# RPi_shield.net
KiCad netlist of a schematic drawn in EAGLE
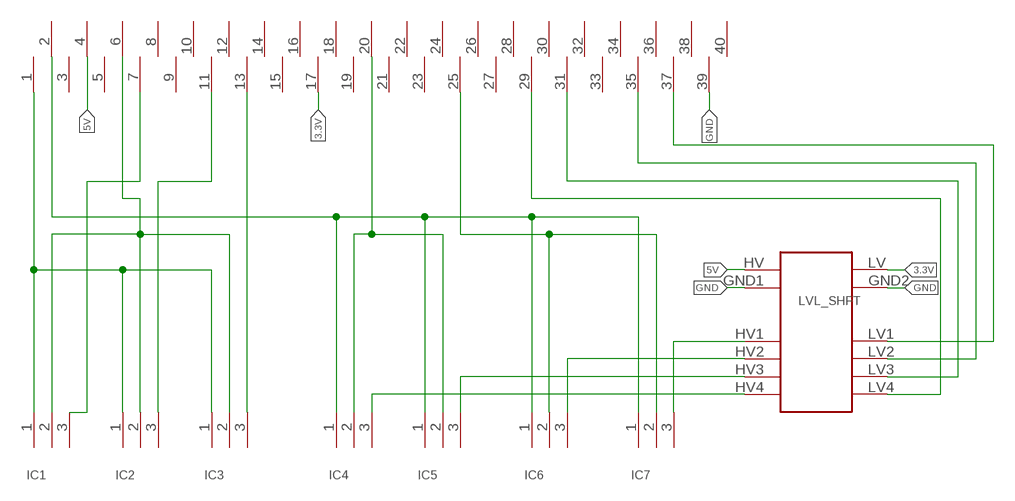
[diagram p0: schematic, sheet 1]

(export (version "E")
  (design (tool "Eeschema 10.0.6"))
  (components
    (comp (ref "IC1")
      (value "3,5MM_3PIN")
      (footprint "eagle-import:3,5MM_3PIN")
      (libsource (lib "eagle-import") (part "3,5MM_3PIN"))
    )
    (comp (ref "IC2")
      (value "3,5MM_3PIN")
      (footprint "eagle-import:3,5MM_3PIN")
      (libsource (lib "eagle-import") (part "3,5MM_3PIN"))
    )
    (comp (ref "IC3")
      (value "3,5MM_3PIN")
      (footprint "eagle-import:3,5MM_3PIN")
      (libsource (lib "eagle-import") (part "3,5MM_3PIN"))
    )
    (comp (ref "IC4")
      (value "3,5MM_3PIN")
      (footprint "eagle-import:3,5MM_3PIN")
      (libsource (lib "eagle-import") (part "3,5MM_3PIN"))
    )
    (comp (ref "IC5")
      (value "3,5MM_3PIN")
      (footprint "eagle-import:3,5MM_3PIN")
      (libsource (lib "eagle-import") (part "3,5MM_3PIN"))
    )
    (comp (ref "IC6")
      (value "3,5MM_3PIN")
      (footprint "eagle-import:3,5MM_3PIN")
      (libsource (lib "eagle-import") (part "3,5MM_3PIN"))
    )
    (comp (ref "IC7")
      (value "3,5MM_3PIN")
      (footprint "eagle-import:3,5MM_3PIN")
      (libsource (lib "eagle-import") (part "3,5MM_3PIN"))
    )
    (comp (ref "IC17")
      (value "40_PIN_2.54MM")
      (footprint "eagle-import:40_PIN_2.54MM")
      (libsource (lib "eagle-import") (part "40_PIN_2.54MM"))
    )
    (comp (ref "LVL_SHFT")
      (value "LVL_SHIFTER_4CH")
      (footprint "eagle-import:LVL_SHIFTER_4CH")
      (libsource (lib "eagle-import") (part "LVL_SHIFTER_4CH"))
    )
  )
  (nets
    (net (code "1") (name "3.3V") (class "Default")
      (node (ref "IC17") (pin "17") (pinfunction "P$17_17") (pintype "bidirectional"))
      (node (ref "LVL_SHFT") (pin "LV") (pinfunction "LV_LV") (pintype "bidirectional"))
    )
    (net (code "2") (name "5V") (class "Default")
      (node (ref "IC17") (pin "4") (pinfunction "P$4_4") (pintype "bidirectional"))
      (node (ref "LVL_SHFT") (pin "HV") (pinfunction "HV_HV") (pintype "bidirectional"))
    )
    (net (code "3") (name "GND") (class "Default")
      (node (ref "IC17") (pin "39") (pinfunction "P$39_39") (pintype "bidirectional"))
      (node (ref "LVL_SHFT") (pin "GND1") (pinfunction "GND1_GND1") (pintype "bidirectional"))
      (node (ref "LVL_SHFT") (pin "GND2") (pinfunction "GND2_GND2") (pintype "bidirectional"))
    )
    (net (code "4") (name "Net-(IC1-P$1)") (class "Default")
      (node (ref "IC1") (pin "1") (pinfunction "P$1_1") (pintype "bidirectional"))
      (node (ref "IC17") (pin "1") (pinfunction "P$1_1") (pintype "bidirectional"))
      (node (ref "IC2") (pin "1") (pinfunction "P$1_1") (pintype "bidirectional"))
      (node (ref "IC3") (pin "1") (pinfunction "P$1_1") (pintype "bidirectional"))
    )
    (net (code "5") (name "Net-(IC1-P$2)") (class "Default")
      (node (ref "IC1") (pin "2") (pinfunction "P$2_2") (pintype "bidirectional"))
      (node (ref "IC17") (pin "6") (pinfunction "P$6_6") (pintype "bidirectional"))
      (node (ref "IC2") (pin "2") (pinfunction "P$2_2") (pintype "bidirectional"))
      (node (ref "IC3") (pin "2") (pinfunction "P$2_2") (pintype "bidirectional"))
    )
    (net (code "6") (name "Net-(IC1-P$3)") (class "Default")
      (node (ref "IC1") (pin "3") (pinfunction "P$3_3") (pintype "bidirectional"))
      (node (ref "IC17") (pin "7") (pinfunction "P$7_7") (pintype "bidirectional"))
    )
    (net (code "7") (name "Net-(IC4-P$3)") (class "Default")
      (node (ref "IC4") (pin "3") (pinfunction "P$3_3") (pintype "bidirectional"))
      (node (ref "LVL_SHFT") (pin "HV4") (pinfunction "HV4_HV4") (pintype "bidirectional"))
    )
    (net (code "8") (name "Net-(IC5-P$3)") (class "Default")
      (node (ref "IC5") (pin "3") (pinfunction "P$3_3") (pintype "bidirectional"))
      (node (ref "LVL_SHFT") (pin "HV3") (pinfunction "HV3_HV3") (pintype "bidirectional"))
    )
    (net (code "9") (name "Net-(IC6-P$3)") (class "Default")
      (node (ref "IC6") (pin "3") (pinfunction "P$3_3") (pintype "bidirectional"))
      (node (ref "LVL_SHFT") (pin "HV2") (pinfunction "HV2_HV2") (pintype "bidirectional"))
    )
    (net (code "10") (name "Net-(IC7-P$3)") (class "Default")
      (node (ref "IC7") (pin "3") (pinfunction "P$3_3") (pintype "bidirectional"))
      (node (ref "LVL_SHFT") (pin "HV1") (pinfunction "HV1_HV1") (pintype "bidirectional"))
    )
    (net (code "11") (name "Net-(IC17-P$2)") (class "Default")
      (node (ref "IC17") (pin "2") (pinfunction "P$2_2") (pintype "bidirectional"))
      (node (ref "IC4") (pin "1") (pinfunction "P$1_1") (pintype "bidirectional"))
      (node (ref "IC5") (pin "1") (pinfunction "P$1_1") (pintype "bidirectional"))
      (node (ref "IC6") (pin "1") (pinfunction "P$1_1") (pintype "bidirectional"))
      (node (ref "IC7") (pin "1") (pinfunction "P$1_1") (pintype "bidirectional"))
    )
    (net (code "12") (name "Net-(IC17-P$11)") (class "Default")
      (node (ref "IC17") (pin "11") (pinfunction "P$11_11") (pintype "bidirectional"))
      (node (ref "IC2") (pin "3") (pinfunction "P$3_3") (pintype "bidirectional"))
    )
    (net (code "13") (name "Net-(IC17-P$13)") (class "Default")
      (node (ref "IC17") (pin "13") (pinfunction "P$13_13") (pintype "bidirectional"))
      (node (ref "IC3") (pin "3") (pinfunction "P$3_3") (pintype "bidirectional"))
    )
    (net (code "14") (name "Net-(IC17-P$20)") (class "Default")
      (node (ref "IC17") (pin "20") (pinfunction "P$20_20") (pintype "bidirectional"))
      (node (ref "IC4") (pin "2") (pinfunction "P$2_2") (pintype "bidirectional"))
      (node (ref "IC5") (pin "2") (pinfunction "P$2_2") (pintype "bidirectional"))
    )
    (net (code "15") (name "Net-(IC17-P$25)") (class "Default")
      (node (ref "IC17") (pin "25") (pinfunction "P$25_25") (pintype "bidirectional"))
      (node (ref "IC6") (pin "2") (pinfunction "P$2_2") (pintype "bidirectional"))
      (node (ref "IC7") (pin "2") (pinfunction "P$2_2") (pintype "bidirectional"))
    )
    (net (code "16") (name "Net-(IC17-P$29)") (class "Default")
      (node (ref "IC17") (pin "29") (pinfunction "P$29_29") (pintype "bidirectional"))
      (node (ref "LVL_SHFT") (pin "LV4") (pinfunction "LV4_LV4") (pintype "bidirectional"))
    )
    (net (code "17") (name "Net-(IC17-P$31)") (class "Default")
      (node (ref "IC17") (pin "31") (pinfunction "P$31_31") (pintype "bidirectional"))
      (node (ref "LVL_SHFT") (pin "LV3") (pinfunction "LV3_LV3") (pintype "bidirectional"))
    )
    (net (code "18") (name "Net-(IC17-P$35)") (class "Default")
      (node (ref "IC17") (pin "35") (pinfunction "P$35_35") (pintype "bidirectional"))
      (node (ref "LVL_SHFT") (pin "LV2") (pinfunction "LV2_LV2") (pintype "bidirectional"))
    )
    (net (code "19") (name "Net-(IC17-P$37)") (class "Default")
      (node (ref "IC17") (pin "37") (pinfunction "P$37_37") (pintype "bidirectional"))
      (node (ref "LVL_SHFT") (pin "LV1") (pinfunction "LV1_LV1") (pintype "bidirectional"))
    )
    (net (code "20") (name "unconnected-(IC17-P$3-Pad3)") (class "Default")
      (node (ref "IC17") (pin "3") (pinfunction "P$3_3") (pintype "bidirectional"))
    )
    (net (code "21") (name "unconnected-(IC17-P$5-Pad5)") (class "Default")
      (node (ref "IC17") (pin "5") (pinfunction "P$5_5") (pintype "bidirectional"))
    )
    (net (code "22") (name "unconnected-(IC17-P$8-Pad8)") (class "Default")
      (node (ref "IC17") (pin "8") (pinfunction "P$8_8") (pintype "bidirectional"))
    )
    (net (code "23") (name "unconnected-(IC17-P$9-Pad9)") (class "Default")
      (node (ref "IC17") (pin "9") (pinfunction "P$9_9") (pintype "bidirectional"))
    )
    (net (code "24") (name "unconnected-(IC17-P$10-Pad10)") (class "Default")
      (node (ref "IC17") (pin "10") (pinfunction "P$10_10") (pintype "bidirectional"))
    )
    (net (code "25") (name "unconnected-(IC17-P$12-Pad12)") (class "Default")
      (node (ref "IC17") (pin "12") (pinfunction "P$12_12") (pintype "bidirectional"))
    )
    (net (code "26") (name "unconnected-(IC17-P$14-Pad14)") (class "Default")
      (node (ref "IC17") (pin "14") (pinfunction "P$14_14") (pintype "bidirectional"))
    )
    (net (code "27") (name "unconnected-(IC17-P$15-Pad15)") (class "Default")
      (node (ref "IC17") (pin "15") (pinfunction "P$15_15") (pintype "bidirectional"))
    )
    (net (code "28") (name "unconnected-(IC17-P$16-Pad16)") (class "Default")
      (node (ref "IC17") (pin "16") (pinfunction "P$16_16") (pintype "bidirectional"))
    )
    (net (code "29") (name "unconnected-(IC17-P$18-Pad18)") (class "Default")
      (node (ref "IC17") (pin "18") (pinfunction "P$18_18") (pintype "bidirectional"))
    )
    (net (code "30") (name "unconnected-(IC17-P$19-Pad19)") (class "Default")
      (node (ref "IC17") (pin "19") (pinfunction "P$19_19") (pintype "bidirectional"))
    )
    (net (code "31") (name "unconnected-(IC17-P$21-Pad21)") (class "Default")
      (node (ref "IC17") (pin "21") (pinfunction "P$21_21") (pintype "bidirectional"))
    )
    (net (code "32") (name "unconnected-(IC17-P$22-Pad22)") (class "Default")
      (node (ref "IC17") (pin "22") (pinfunction "P$22_22") (pintype "bidirectional"))
    )
    (net (code "33") (name "unconnected-(IC17-P$23-Pad23)") (class "Default")
      (node (ref "IC17") (pin "23") (pinfunction "P$23_23") (pintype "bidirectional"))
    )
    (net (code "34") (name "unconnected-(IC17-P$24-Pad24)") (class "Default")
      (node (ref "IC17") (pin "24") (pinfunction "P$24_24") (pintype "bidirectional"))
    )
    (net (code "35") (name "unconnected-(IC17-P$26-Pad26)") (class "Default")
      (node (ref "IC17") (pin "26") (pinfunction "P$26_26") (pintype "bidirectional"))
    )
    (net (code "36") (name "unconnected-(IC17-P$27-Pad27)") (class "Default")
      (node (ref "IC17") (pin "27") (pinfunction "P$27_27") (pintype "bidirectional"))
    )
    (net (code "37") (name "unconnected-(IC17-P$28-Pad28)") (class "Default")
      (node (ref "IC17") (pin "28") (pinfunction "P$28_28") (pintype "bidirectional"))
    )
    (net (code "38") (name "unconnected-(IC17-P$30-Pad30)") (class "Default")
      (node (ref "IC17") (pin "30") (pinfunction "P$30_30") (pintype "bidirectional"))
    )
    (net (code "39") (name "unconnected-(IC17-P$32-Pad32)") (class "Default")
      (node (ref "IC17") (pin "32") (pinfunction "P$32_32") (pintype "bidirectional"))
    )
    (net (code "40") (name "unconnected-(IC17-P$33-Pad33)") (class "Default")
      (node (ref "IC17") (pin "33") (pinfunction "P$33_33") (pintype "bidirectional"))
    )
    (net (code "41") (name "unconnected-(IC17-P$34-Pad34)") (class "Default")
      (node (ref "IC17") (pin "34") (pinfunction "P$34_34") (pintype "bidirectional"))
    )
    (net (code "42") (name "unconnected-(IC17-P$36-Pad36)") (class "Default")
      (node (ref "IC17") (pin "36") (pinfunction "P$36_36") (pintype "bidirectional"))
    )
    (net (code "43") (name "unconnected-(IC17-P$38-Pad38)") (class "Default")
      (node (ref "IC17") (pin "38") (pinfunction "P$38_38") (pintype "bidirectional"))
    )
    (net (code "44") (name "unconnected-(IC17-P$40-Pad40)") (class "Default")
      (node (ref "IC17") (pin "40") (pinfunction "P$40_40") (pintype "bidirectional"))
    )
  )
)
